# USB2_0_Host_Connectors.net
KiCad netlist of a schematic drawn in Altium Designer
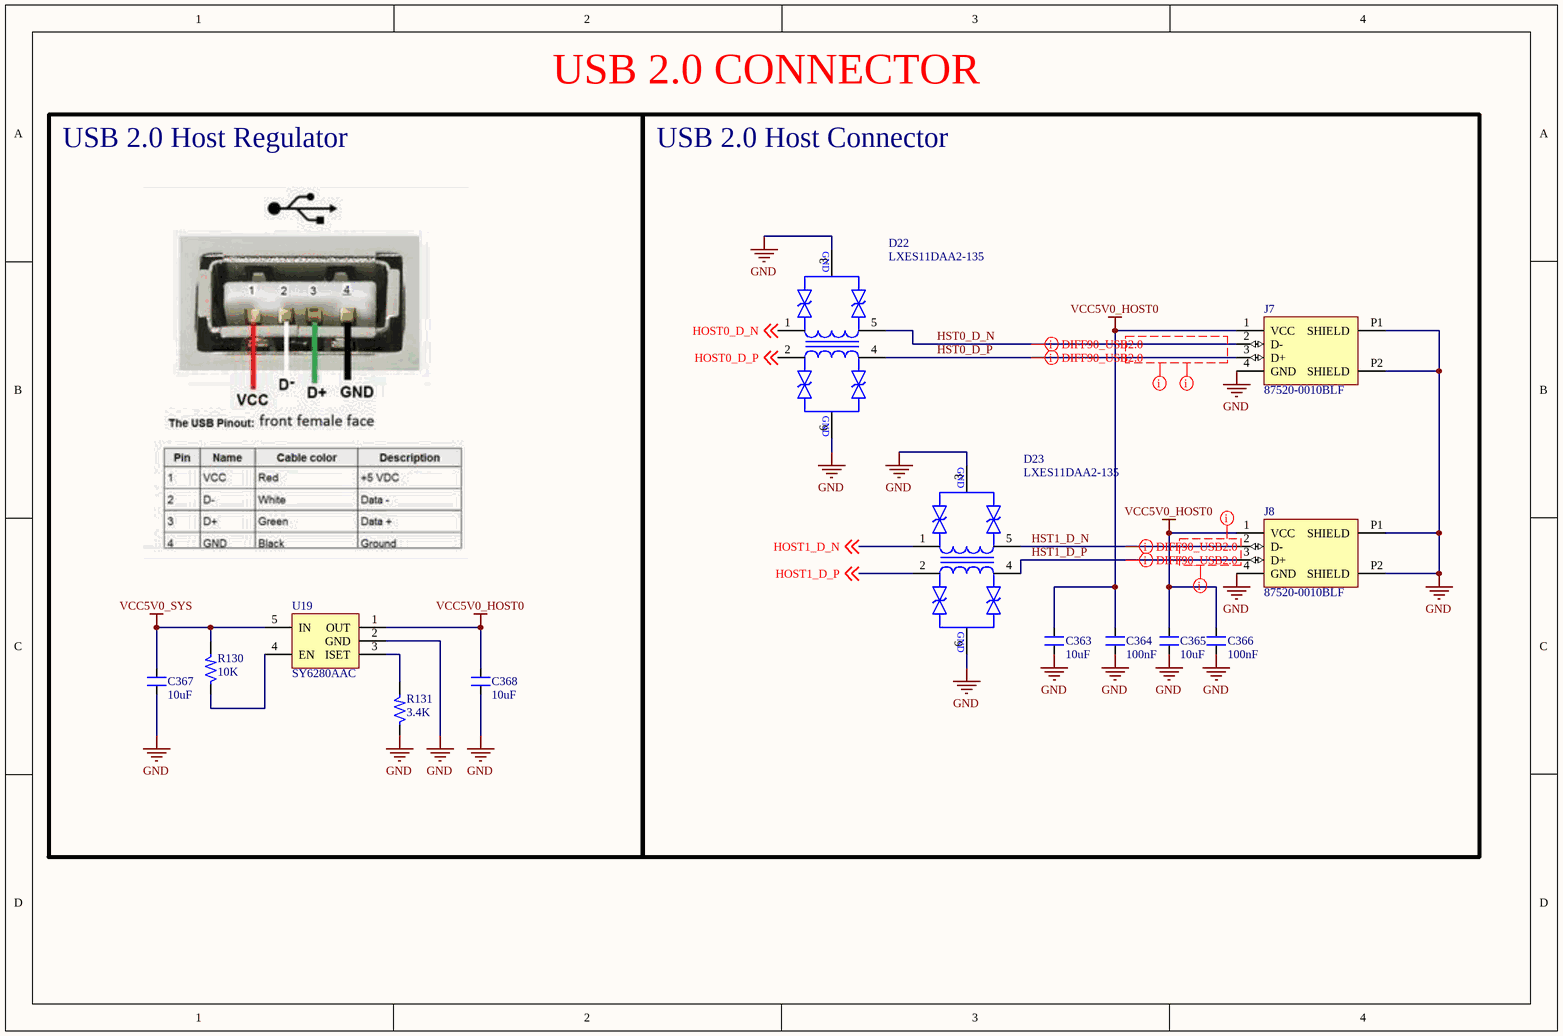
[diagram p0: USB2.0 Host Connectors.SchDoc]

(export (version "E")
  (design (tool "Eeschema 10.0.6"))
  (components
    (comp (ref "C363")
      (value "10uF")
      (footprint "CAP_0805")
      (description "10µF ±10% 25V Ceramic Capacitor X5R 0805 (2012 Metric)")
      (fields
        (field (name "MANUFACTURER") "Murata Electronics")
        (field (name "MANUFACTURER PART NUMBER") "GRM21BR61E106KA73K")
      )
      (libsource (lib "RK3399 _Module_Schlib") (part "CAP_10uF-25V-10%-0805"))
    )
    (comp (ref "C364")
      (value "100nF")
      (footprint "CAP_0805")
      (description "0.1µF ±10% 25V Ceramic Capacitor X7R 0805 (2012 Metric)")
      (fields
        (field (name "MANUFACTURER") "Yageo")
        (field (name "MANUFACTURER PART NUMBER") "CC0805KRX7R8BB104")
      )
      (libsource (lib "RK3399 _Module_Schlib") (part "CAP_100nF-25V-10%-0805"))
    )
    (comp (ref "C365")
      (value "10uF")
      (footprint "CAP_0805")
      (description "10µF ±10% 25V Ceramic Capacitor X5R 0805 (2012 Metric)")
      (fields
        (field (name "MANUFACTURER") "Murata Electronics")
        (field (name "MANUFACTURER PART NUMBER") "GRM21BR61E106KA73K")
      )
      (libsource (lib "RK3399 _Module_Schlib") (part "CAP_10uF-25V-10%-0805"))
    )
    (comp (ref "C366")
      (value "100nF")
      (footprint "CAP_0805")
      (description "0.1µF ±10% 25V Ceramic Capacitor X7R 0805 (2012 Metric)")
      (fields
        (field (name "MANUFACTURER") "Yageo")
        (field (name "MANUFACTURER PART NUMBER") "CC0805KRX7R8BB104")
      )
      (libsource (lib "RK3399 _Module_Schlib") (part "CAP_100nF-25V-10%-0805"))
    )
    (comp (ref "C367")
      (value "10uF")
      (footprint "CAP_0805")
      (description "10µF ±10% 25V Ceramic Capacitor X5R 0805 (2012 Metric)")
      (fields
        (field (name "MANUFACTURER") "Murata Electronics")
        (field (name "MANUFACTURER PART NUMBER") "GRM21BR61E106KA73K")
      )
      (libsource (lib "RK3399 _Module_Schlib") (part "CAP_10uF-25V-10%-0805"))
    )
    (comp (ref "C368")
      (value "10uF")
      (footprint "CAP_0805")
      (description "10µF ±10% 25V Ceramic Capacitor X5R 0805 (2012 Metric)")
      (fields
        (field (name "MANUFACTURER") "Murata Electronics")
        (field (name "MANUFACTURER PART NUMBER") "GRM21BR61E106KA73K")
      )
      (libsource (lib "RK3399 _Module_Schlib") (part "CAP_10uF-25V-10%-0805"))
    )
    (comp (ref "D22")
      (value "LXES11DAA2-135")
      (footprint "DIO_LXES11D_SMD")
      (description "Clamp Ipp Tvs Diode Surface Mount 10-SMD")
      (fields (field (name "MANUFACTURER") "Murata Electronics"))
      (libsource (lib "RK3399 _Module_Schlib") (part "DIO-T-A_5V-6SMD"))
    )
    (comp (ref "D23")
      (value "LXES11DAA2-135")
      (footprint "DIO_LXES11D_SMD")
      (description "Clamp Ipp Tvs Diode Surface Mount 10-SMD")
      (fields (field (name "MANUFACTURER") "Murata Electronics"))
      (libsource (lib "RK3399 _Module_Schlib") (part "DIO-T-A_5V-6SMD"))
    )
    (comp (ref "J7")
      (value "87520-0010BLF")
      (footprint "CON4_614004134726_TH")
      (description "USB-A (USB TYPE-A) USB 2.0 Receptacle Connector 4 Position Through Hole, Right Angle")
      (fields (field (name "MANUFACTURER") "Amphenol ICC (FCI)"))
      (libsource (lib "EsteemPCB_COB_Course_intlib") (part "CON-SKT-USB_87520-0010BLF-RA-TH"))
    )
    (comp (ref "J8")
      (value "87520-0010BLF")
      (footprint "CON4_614004134726_TH")
      (description "USB-A (USB TYPE-A) USB 2.0 Receptacle Connector 4 Position Through Hole, Right Angle")
      (fields (field (name "MANUFACTURER") "Amphenol ICC (FCI)"))
      (libsource (lib "EsteemPCB_COB_Course_intlib") (part "CON-SKT-USB_87520-0010BLF-RA-TH"))
    )
    (comp (ref "R130")
      (value "10K")
      (footprint "RES_0603")
      (description "10 kOhms ±1% 0.1W, 1/10W Chip Resistor 0603 (1608 Metric) Thick Film")
      (fields
        (field (name "MANUFACTURER") "Yageo")
        (field (name "MANUFACTURER PART NUMBER") "RC0603FR-0710KL")
      )
      (libsource (lib "RK3399 _Module_Schlib") (part "RES_10K-0.1W-1%-0603"))
    )
    (comp (ref "R131")
      (value "3.4K")
      (footprint "RES_0603")
      (description "3.4 kOhms ±1% 0.1W, 1/10W Chip Resistor 0603 (1608 Metric) Automotive AEC-Q200 Thick Film")
      (fields
        (field (name "MANUFACTURER") "Stackpole Electronics Inc")
        (field (name "MANUFACTURER PART NUMBER") "RMCF0603FT3K40")
      )
      (libsource (lib "RK3399 _Module_Schlib") (part "RES_3.4K-0.1W-1%-0603"))
    )
    (comp (ref "U19")
      (value "SY6280AAC")
      (footprint "SOT23-5")
      (description "SOT-23-5 PMIC - Power Distribution Switches RoHS")
      (fields (field (name "MANUFACTURER") "Silergy Corp"))
      (libsource (lib "RK3399 _Module_Schlib") (part "REG-ADJ_5.5V-5.5V-1.25A-SOT-23-5"))
    )
  )
  (nets
    (net (code "1") (name "/HST0_D_N") (class "Default")
      (node (ref "D22") (pin "5") (pinfunction "5_5") (pintype "passive"))
      (node (ref "J7") (pin "2") (pinfunction "D-_2") (pintype "bidirectional"))
    )
    (net (code "2") (name "/HST0_D_P") (class "Default")
      (node (ref "D22") (pin "4") (pinfunction "4_4") (pintype "passive"))
      (node (ref "J7") (pin "3") (pinfunction "D+_3") (pintype "bidirectional"))
    )
    (net (code "3") (name "/HST1_D_N") (class "Default")
      (node (ref "D23") (pin "5") (pinfunction "5_5") (pintype "passive"))
      (node (ref "J8") (pin "2") (pinfunction "D-_2") (pintype "bidirectional"))
    )
    (net (code "4") (name "/HST1_D_P") (class "Default")
      (node (ref "D23") (pin "4") (pinfunction "4_4") (pintype "passive"))
      (node (ref "J8") (pin "3") (pinfunction "D+_3") (pintype "bidirectional"))
    )
    (net (code "5") (name "GND") (class "Default")
      (node (ref "C363") (pin "1") (pinfunction "1_1") (pintype "passive"))
      (node (ref "C364") (pin "1") (pinfunction "1_1") (pintype "passive"))
      (node (ref "C365") (pin "1") (pinfunction "1_1") (pintype "passive"))
      (node (ref "C366") (pin "1") (pinfunction "1_1") (pintype "passive"))
      (node (ref "C367") (pin "1") (pinfunction "1_1") (pintype "passive"))
      (node (ref "C368") (pin "1") (pinfunction "1_1") (pintype "passive"))
      (node (ref "D22") (pin "3") (pinfunction "5_3") (pintype "passive"))
      (node (ref "D22") (pin "6") (pinfunction "6_6") (pintype "passive"))
      (node (ref "D23") (pin "3") (pinfunction "5_3") (pintype "passive"))
      (node (ref "D23") (pin "6") (pinfunction "6_6") (pintype "passive"))
      (node (ref "J7") (pin "4") (pinfunction "GND_4") (pintype "power_in"))
      (node (ref "J7") (pin "P1") (pinfunction "SHIELD_P1") (pintype "passive"))
      (node (ref "J7") (pin "P2") (pinfunction "SHIELD_P2") (pintype "passive"))
      (node (ref "J8") (pin "4") (pinfunction "GND_4") (pintype "power_in"))
      (node (ref "J8") (pin "P1") (pinfunction "SHIELD_P1") (pintype "passive"))
      (node (ref "J8") (pin "P2") (pinfunction "SHIELD_P2") (pintype "passive"))
      (node (ref "R131") (pin "1") (pinfunction "1_1") (pintype "passive"))
      (node (ref "U19") (pin "2") (pinfunction "GND_2") (pintype "passive"))
    )
    (net (code "6") (name "HOST0_D_N") (class "Default")
      (node (ref "D22") (pin "1") (pinfunction "1_1") (pintype "passive"))
    )
    (net (code "7") (name "HOST0_D_P") (class "Default")
      (node (ref "D22") (pin "2") (pinfunction "2_2") (pintype "passive"))
    )
    (net (code "8") (name "HOST1_D_N") (class "Default")
      (node (ref "D23") (pin "1") (pinfunction "1_1") (pintype "passive"))
    )
    (net (code "9") (name "HOST1_D_P") (class "Default")
      (node (ref "D23") (pin "2") (pinfunction "2_2") (pintype "passive"))
    )
    (net (code "10") (name "Net-(U19-EN)") (class "Default")
      (node (ref "R130") (pin "1") (pinfunction "1_1") (pintype "passive"))
      (node (ref "U19") (pin "4") (pinfunction "EN_4") (pintype "passive"))
    )
    (net (code "11") (name "Net-(U19-ISET)") (class "Default")
      (node (ref "R131") (pin "2") (pinfunction "2_2") (pintype "passive"))
      (node (ref "U19") (pin "3") (pinfunction "ISET_3") (pintype "passive"))
    )
    (net (code "12") (name "VCC5V0_HOST0") (class "Default")
      (node (ref "C363") (pin "2") (pinfunction "2_2") (pintype "passive"))
      (node (ref "C364") (pin "2") (pinfunction "2_2") (pintype "passive"))
      (node (ref "C365") (pin "2") (pinfunction "2_2") (pintype "passive"))
      (node (ref "C366") (pin "2") (pinfunction "2_2") (pintype "passive"))
      (node (ref "C368") (pin "2") (pinfunction "2_2") (pintype "passive"))
      (node (ref "J7") (pin "1") (pinfunction "VCC_1") (pintype "power_in"))
      (node (ref "J8") (pin "1") (pinfunction "VCC_1") (pintype "power_in"))
      (node (ref "U19") (pin "1") (pinfunction "OUT_1") (pintype "passive"))
    )
    (net (code "13") (name "VCC5V0_SYS") (class "Default")
      (node (ref "C367") (pin "2") (pinfunction "2_2") (pintype "passive"))
      (node (ref "R130") (pin "2") (pinfunction "2_2") (pintype "passive"))
      (node (ref "U19") (pin "5") (pinfunction "IN_5") (pintype "passive"))
    )
  )
)
